# atmega328pTest.net
KiCad netlist of a schematic drawn in EAGLE
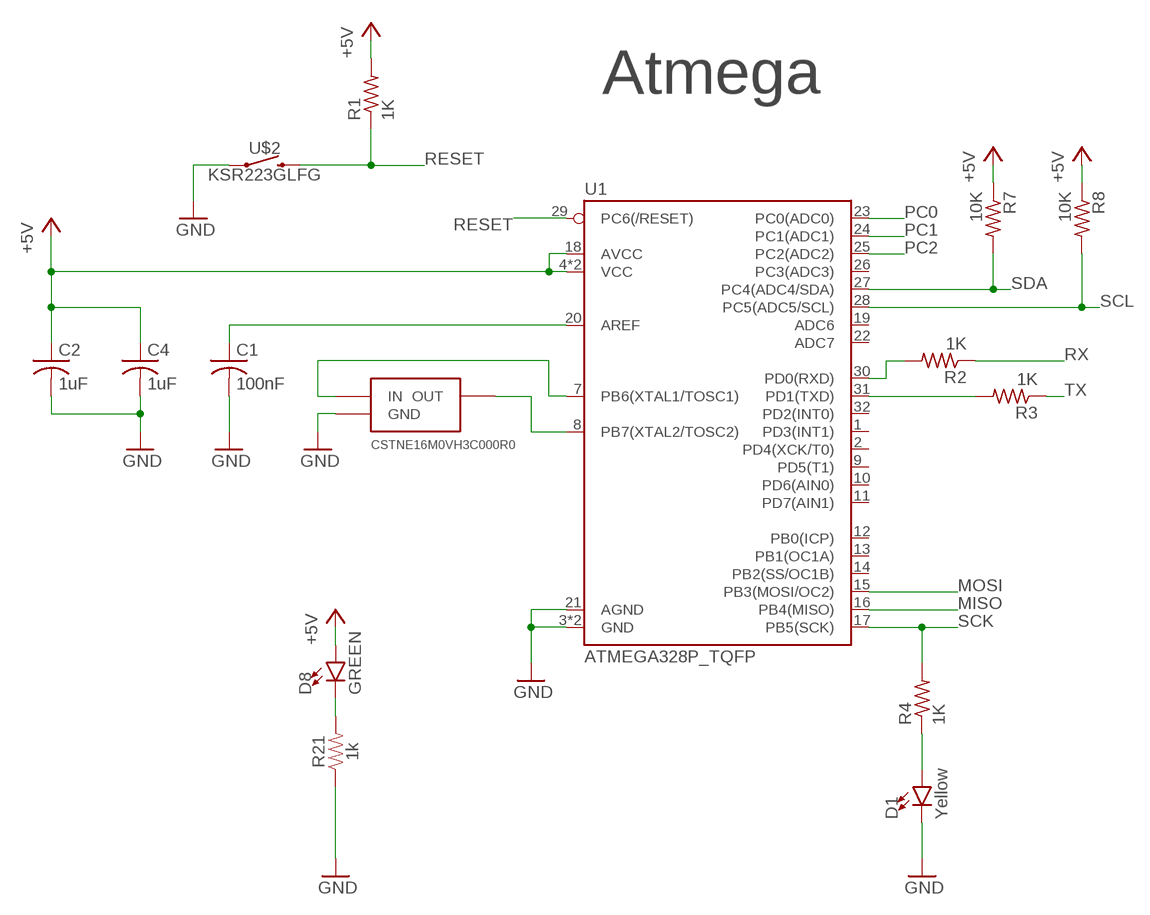
[diagram p0: schematic, sheet 1, part 1 of 2]
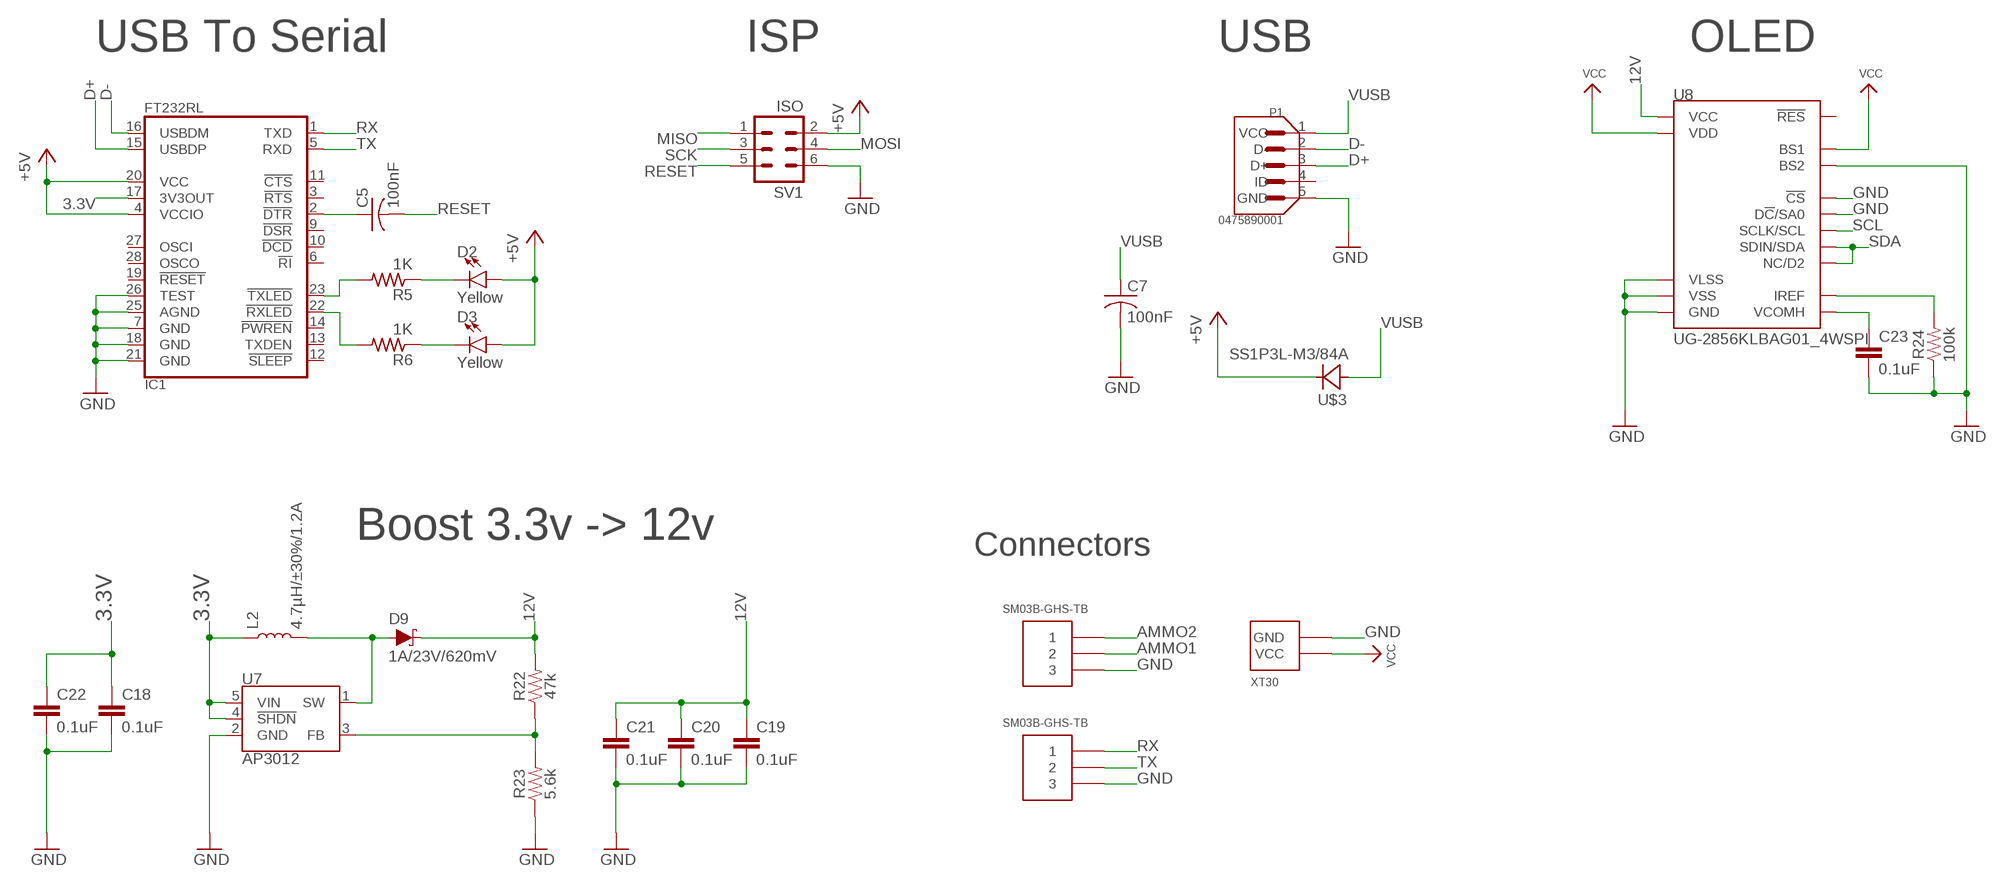
[diagram p1: schematic, sheet 1, part 2 of 2]

(export (version "E")
  (design (tool "Eeschema 10.0.6"))
  (components
    (comp (ref "C1")
      (value "100nF")
      (footprint "eagle-import:C0603")
      (libsource (lib "eagle-import") (part "C-USC0603"))
    )
    (comp (ref "C2")
      (value "1uF")
      (footprint "eagle-import:C0603")
      (libsource (lib "eagle-import") (part "C-USC0603"))
    )
    (comp (ref "C4")
      (value "1uF")
      (footprint "eagle-import:C0603")
      (libsource (lib "eagle-import") (part "C-USC0603"))
    )
    (comp (ref "C5")
      (value "100nF")
      (footprint "eagle-import:C0603")
      (libsource (lib "eagle-import") (part "C-USC0603"))
    )
    (comp (ref "C7")
      (value "100nF")
      (footprint "eagle-import:C0603")
      (libsource (lib "eagle-import") (part "C-USC0603"))
    )
    (comp (ref "C18")
      (value "0.1uF")
      (footprint "eagle-import:0603")
      (libsource (lib "eagle-import") (part "0.1UF-0603-25V-(+80/-20%)"))
    )
    (comp (ref "C19")
      (value "0.1uF")
      (footprint "eagle-import:0603")
      (libsource (lib "eagle-import") (part "0.1UF-0603-25V-(+80/-20%)"))
    )
    (comp (ref "C20")
      (value "0.1uF")
      (footprint "eagle-import:0603")
      (libsource (lib "eagle-import") (part "0.1UF-0603-25V-(+80/-20%)"))
    )
    (comp (ref "C21")
      (value "0.1uF")
      (footprint "eagle-import:0603")
      (libsource (lib "eagle-import") (part "0.1UF-0603-25V-(+80/-20%)"))
    )
    (comp (ref "C22")
      (value "0.1uF")
      (footprint "eagle-import:0603")
      (libsource (lib "eagle-import") (part "0.1UF-0603-25V-(+80/-20%)"))
    )
    (comp (ref "C23")
      (value "0.1uF")
      (footprint "eagle-import:0603")
      (libsource (lib "eagle-import") (part "0.1UF-0603-25V-(+80/-20%)"))
    )
    (comp (ref "D1")
      (value "Yellow")
      (footprint "eagle-import:LED-0603")
      (libsource (lib "eagle-import") (part "LED0603"))
    )
    (comp (ref "D2")
      (value "Yellow")
      (footprint "eagle-import:LED-0603")
      (libsource (lib "eagle-import") (part "LED0603"))
    )
    (comp (ref "D3")
      (value "Yellow")
      (footprint "eagle-import:LED-0603")
      (libsource (lib "eagle-import") (part "LED0603"))
    )
    (comp (ref "D8")
      (value "GREEN")
      (footprint "eagle-import:LED-0603")
      (libsource (lib "eagle-import") (part "SparkFun-LED_529_LED0603"))
    )
    (comp (ref "D9")
      (value "1A/23V/620mV")
      (footprint "eagle-import:SOD-323")
      (libsource (lib "eagle-import") (part "DIODE-SCHOTTKY-BAT20J"))
    )
    (comp (ref "IC1")
      (value "FT232RL")
      (footprint "eagle-import:SSOP28-LD")
      (fields (field (name "DIGI-KEY_PART_NUMBER") "768-1007-1-ND") (field (name "MF") "FTDI, Future"))
      (libsource (lib "eagle-import") (part "FT232RL"))
    )
    (comp (ref "L2")
      (value "4.7µH/±30%/1.2A")
      (footprint "eagle-import:INDUCTOR_4.7UH")
      (libsource (lib "eagle-import") (part "INDUCTOR-CDRH-4.7UH"))
    )
    (comp (ref "P1")
      (value "0475890001")
      (footprint "eagle-import:MOLEX_0475890001")
      (fields (field (name "DIGI-KEY_PART_NUMBER") "WM17143CT-ND") (field (name "MF") "Molex"))
      (libsource (lib "eagle-import") (part "0475890001"))
    )
    (comp (ref "R1")
      (value "1K")
      (footprint "eagle-import:R0603")
      (libsource (lib "eagle-import") (part "R-US_R0603"))
    )
    (comp (ref "R2")
      (value "1K")
      (footprint "eagle-import:R0603")
      (libsource (lib "eagle-import") (part "R-US_R0603"))
    )
    (comp (ref "R3")
      (value "1K")
      (footprint "eagle-import:R0603")
      (libsource (lib "eagle-import") (part "R-US_R0603"))
    )
    (comp (ref "R4")
      (value "1K")
      (footprint "eagle-import:R0603")
      (libsource (lib "eagle-import") (part "R-US_R0603"))
    )
    (comp (ref "R5")
      (value "1K")
      (footprint "eagle-import:R0603")
      (libsource (lib "eagle-import") (part "R-US_R0603"))
    )
    (comp (ref "R6")
      (value "1K")
      (footprint "eagle-import:R0603")
      (libsource (lib "eagle-import") (part "R-US_R0603"))
    )
    (comp (ref "R7")
      (value "10K")
      (footprint "eagle-import:R0603")
      (libsource (lib "eagle-import") (part "R-US_R0603"))
    )
    (comp (ref "R8")
      (value "10K")
      (footprint "eagle-import:R0603")
      (libsource (lib "eagle-import") (part "R-US_R0603"))
    )
    (comp (ref "R21")
      (value "1k")
      (footprint "eagle-import:0603")
      (libsource (lib "eagle-import") (part "1KOHM-0603-1/10W-1%"))
    )
    (comp (ref "R22")
      (value "47k")
      (footprint "eagle-import:0603")
      (libsource (lib "eagle-import") (part "47KOHM-0603-1/10W-1%"))
    )
    (comp (ref "R23")
      (value "5.6k")
      (footprint "eagle-import:0603")
      (libsource (lib "eagle-import") (part "5.6KOHM-0603-1/10W-1%"))
    )
    (comp (ref "R24")
      (value "100k")
      (footprint "eagle-import:0603")
      (libsource (lib "eagle-import") (part "100KOHM-0603-1/10W-1%"))
    )
    (comp (ref "SV1")
      (value "ISO")
      (footprint "eagle-import:MA03-2")
      (libsource (lib "eagle-import") (part "MA03-2"))
    )
    (comp (ref "U$1")
      (value "CSTNE16M0VH3C000R0")
      (footprint "eagle-import:CSTNE16M0VH3C000R0")
      (libsource (lib "eagle-import") (part "CSTNE16M0VH3C000R0"))
    )
    (comp (ref "U$2")
      (value "KSR223GLFG")
      (footprint "eagle-import:KSR223GLFG")
      (libsource (lib "eagle-import") (part "KSR223GLFG"))
    )
    (comp (ref "U$3")
      (value "SS1P3L-M3/84A")
      (footprint "eagle-import:SS1P3L-M3_84A")
      (libsource (lib "eagle-import") (part "SS1P3L-M3/84A"))
    )
    (comp (ref "U$13")
      (value "SM03B-GHS-TB")
      (footprint "eagle-import:SM03B-GHS-TB")
      (libsource (lib "eagle-import") (part "SM03B-GHS-TB"))
    )
    (comp (ref "U$14")
      (value "SM03B-GHS-TB")
      (footprint "eagle-import:SM03B-GHS-TB")
      (libsource (lib "eagle-import") (part "SM03B-GHS-TB"))
    )
    (comp (ref "U$15")
      (value "XT30PW-M")
      (footprint "eagle-import:XT30")
      (libsource (lib "eagle-import") (part "XT30PW-M"))
    )
    (comp (ref "U1")
      (value "ATMEGA328P_TQFP")
      (footprint "eagle-import:TQFP32-08")
      (libsource (lib "eagle-import") (part "ATMEGA328P_TQFP"))
    )
    (comp (ref "U7")
      (value "AP3012")
      (footprint "eagle-import:SOT23-5")
      (libsource (lib "eagle-import") (part "AP3012"))
    )
    (comp (ref "U8")
      (value "UG-2856KLBAG01_4WSPI")
      (footprint "eagle-import:FPC05024-42201")
      (libsource (lib "eagle-import") (part "UG-2856KLBAG01_4WSPI"))
    )
  )
  (nets
    (net (code "1") (name "+5V") (class "Default")
      (node (ref "C2") (pin "1") (pinfunction "1_1") (pintype "passive"))
      (node (ref "C4") (pin "1") (pinfunction "1_1") (pintype "passive"))
      (node (ref "D2") (pin "A") (pinfunction "A_A") (pintype "passive"))
      (node (ref "D3") (pin "A") (pinfunction "A_A") (pintype "passive"))
      (node (ref "D8") (pin "A") (pinfunction "A_A") (pintype "passive"))
      (node (ref "IC1") (pin "20") (pinfunction "VCC_20") (pintype "power_in"))
      (node (ref "IC1") (pin "4") (pinfunction "VCCIO_4") (pintype "power_in"))
      (node (ref "R1") (pin "2") (pinfunction "2_2") (pintype "passive"))
      (node (ref "R7") (pin "1") (pinfunction "1_1") (pintype "passive"))
      (node (ref "R8") (pin "1") (pinfunction "1_1") (pintype "passive"))
      (node (ref "SV1") (pin "2") (pinfunction "2_2") (pintype "passive"))
      (node (ref "U$3") (pin "P$1") (pinfunction "C_P$1") (pintype "passive"))
      (node (ref "U1") (pin "18") (pinfunction "AVCC_18") (pintype "bidirectional"))
      (node (ref "U1") (pin "4") (pinfunction "VCC_4") (pintype "bidirectional"))
      (node (ref "U1") (pin "6") (pinfunction "VCC_6") (pintype "bidirectional"))
    )
    (net (code "2") (name "/3.3V") (class "Default")
      (node (ref "C18") (pin "1") (pinfunction "1_1") (pintype "passive"))
      (node (ref "C22") (pin "1") (pinfunction "1_1") (pintype "passive"))
      (node (ref "IC1") (pin "17") (pinfunction "3V3OUT_17") (pintype "power_in"))
      (node (ref "L2") (pin "P$1") (pinfunction "1_P$1") (pintype "passive"))
      (node (ref "U7") (pin "4") (pinfunction "~{SHDN}_4") (pintype "bidirectional"))
      (node (ref "U7") (pin "5") (pinfunction "VIN_5") (pintype "bidirectional"))
    )
    (net (code "3") (name "/12V") (class "Default")
      (node (ref "C19") (pin "1") (pinfunction "1_1") (pintype "passive"))
      (node (ref "C20") (pin "1") (pinfunction "1_1") (pintype "passive"))
      (node (ref "C21") (pin "1") (pinfunction "1_1") (pintype "passive"))
      (node (ref "D9") (pin "C") (pinfunction "C_C") (pintype "passive"))
      (node (ref "R22") (pin "2") (pinfunction "2_2") (pintype "passive"))
      (node (ref "U8") (pin "P$23") (pinfunction "VCC_P$23") (pintype "bidirectional"))
    )
    (net (code "4") (name "/AMMO1") (class "Default")
      (node (ref "U$14") (pin "P$4") (pinfunction "2_P$4") (pintype "bidirectional"))
    )
    (net (code "5") (name "/AMMO2") (class "Default")
      (node (ref "U$14") (pin "P$3") (pinfunction "1_P$3") (pintype "bidirectional"))
    )
    (net (code "6") (name "/D+") (class "Default")
      (node (ref "IC1") (pin "15") (pinfunction "USBDP_15") (pintype "bidirectional"))
      (node (ref "P1") (pin "3") (pinfunction "D+_3") (pintype "bidirectional"))
    )
    (net (code "7") (name "/D-") (class "Default")
      (node (ref "IC1") (pin "16") (pinfunction "USBDM_16") (pintype "bidirectional"))
      (node (ref "P1") (pin "2") (pinfunction "D-_2") (pintype "bidirectional"))
    )
    (net (code "8") (name "/MISO") (class "Default")
      (node (ref "SV1") (pin "1") (pinfunction "1_1") (pintype "passive"))
      (node (ref "U1") (pin "16") (pinfunction "PB4(MISO)_16") (pintype "bidirectional"))
    )
    (net (code "9") (name "/MOSI") (class "Default")
      (node (ref "SV1") (pin "4") (pinfunction "4_4") (pintype "passive"))
      (node (ref "U1") (pin "15") (pinfunction "PB3(MOSI/OC2)_15") (pintype "bidirectional"))
    )
    (net (code "10") (name "/PC0") (class "Default")
      (node (ref "U1") (pin "23") (pinfunction "PC0(ADC0)_23") (pintype "bidirectional"))
    )
    (net (code "11") (name "/PC1") (class "Default")
      (node (ref "U1") (pin "24") (pinfunction "PC1(ADC1)_24") (pintype "bidirectional"))
    )
    (net (code "12") (name "/PC2") (class "Default")
      (node (ref "U1") (pin "25") (pinfunction "PC2(ADC2)_25") (pintype "bidirectional"))
    )
    (net (code "13") (name "/RESET") (class "Default")
      (node (ref "C5") (pin "2") (pinfunction "2_2") (pintype "passive"))
      (node (ref "R1") (pin "1") (pinfunction "1_1") (pintype "passive"))
      (node (ref "SV1") (pin "5") (pinfunction "5_5") (pintype "passive"))
      (node (ref "U$2") (pin "P$2") (pinfunction "2_P$2") (pintype "passive"))
      (node (ref "U1") (pin "29") (pinfunction "PC6(/RESET)_29") (pintype "bidirectional"))
    )
    (net (code "14") (name "/RX") (class "Default")
      (node (ref "IC1") (pin "1") (pinfunction "TXD_1") (pintype "output"))
      (node (ref "R2") (pin "1") (pinfunction "1_1") (pintype "passive"))
      (node (ref "U$13") (pin "P$3") (pinfunction "1_P$3") (pintype "bidirectional"))
    )
    (net (code "15") (name "/SCK") (class "Default")
      (node (ref "R4") (pin "2") (pinfunction "2_2") (pintype "passive"))
      (node (ref "SV1") (pin "3") (pinfunction "3_3") (pintype "passive"))
      (node (ref "U1") (pin "17") (pinfunction "PB5(SCK)_17") (pintype "bidirectional"))
    )
    (net (code "16") (name "/SCL") (class "Default")
      (node (ref "R8") (pin "2") (pinfunction "2_2") (pintype "passive"))
      (node (ref "U1") (pin "28") (pinfunction "PC5(ADC5/SCL)_28") (pintype "bidirectional"))
      (node (ref "U8") (pin "P$13") (pinfunction "SCLK/SCL_P$13") (pintype "bidirectional"))
    )
    (net (code "17") (name "/SDA") (class "Default")
      (node (ref "R7") (pin "2") (pinfunction "2_2") (pintype "passive"))
      (node (ref "U1") (pin "27") (pinfunction "PC4(ADC4/SDA)_27") (pintype "bidirectional"))
      (node (ref "U8") (pin "P$14") (pinfunction "SDIN/SDA_P$14") (pintype "bidirectional"))
      (node (ref "U8") (pin "P$15") (pinfunction "NC/D2_P$15") (pintype "bidirectional"))
    )
    (net (code "18") (name "/TX") (class "Default")
      (node (ref "IC1") (pin "5") (pinfunction "RXD_5") (pintype "input"))
      (node (ref "R3") (pin "1") (pinfunction "1_1") (pintype "passive"))
      (node (ref "U$13") (pin "P$4") (pinfunction "2_P$4") (pintype "bidirectional"))
    )
    (net (code "19") (name "/VUSB") (class "Default")
      (node (ref "C7") (pin "1") (pinfunction "1_1") (pintype "passive"))
      (node (ref "P1") (pin "1") (pinfunction "VCC_1") (pintype "power_in"))
      (node (ref "U$3") (pin "P$2") (pinfunction "A_P$2") (pintype "passive"))
    )
    (net (code "20") (name "GND") (class "Default")
      (node (ref "C1") (pin "2") (pinfunction "2_2") (pintype "passive"))
      (node (ref "C18") (pin "2") (pinfunction "2_2") (pintype "passive"))
      (node (ref "C19") (pin "2") (pinfunction "2_2") (pintype "passive"))
      (node (ref "C2") (pin "2") (pinfunction "2_2") (pintype "passive"))
      (node (ref "C20") (pin "2") (pinfunction "2_2") (pintype "passive"))
      (node (ref "C21") (pin "2") (pinfunction "2_2") (pintype "passive"))
      (node (ref "C22") (pin "2") (pinfunction "2_2") (pintype "passive"))
      (node (ref "C23") (pin "2") (pinfunction "2_2") (pintype "passive"))
      (node (ref "C4") (pin "2") (pinfunction "2_2") (pintype "passive"))
      (node (ref "C7") (pin "2") (pinfunction "2_2") (pintype "passive"))
      (node (ref "D1") (pin "C") (pinfunction "C_C") (pintype "passive"))
      (node (ref "IC1") (pin "18") (pinfunction "GND_18") (pintype "power_in"))
      (node (ref "IC1") (pin "21") (pinfunction "GND_21") (pintype "power_in"))
      (node (ref "IC1") (pin "25") (pinfunction "AGND_25") (pintype "power_in"))
      (node (ref "IC1") (pin "26") (pinfunction "TEST_26") (pintype "input"))
      (node (ref "IC1") (pin "7") (pinfunction "GND_7") (pintype "power_in"))
      (node (ref "P1") (pin "5") (pinfunction "GND_5") (pintype "power_in"))
      (node (ref "R21") (pin "1") (pinfunction "1_1") (pintype "passive"))
      (node (ref "R23") (pin "1") (pinfunction "1_1") (pintype "passive"))
      (node (ref "R24") (pin "1") (pinfunction "1_1") (pintype "passive"))
      (node (ref "SV1") (pin "6") (pinfunction "6_6") (pintype "passive"))
      (node (ref "U$1") (pin "2") (pinfunction "GND_2") (pintype "bidirectional"))
      (node (ref "U$13") (pin "P$5") (pinfunction "3_P$5") (pintype "bidirectional"))
      (node (ref "U$14") (pin "P$5") (pinfunction "3_P$5") (pintype "bidirectional"))
      (node (ref "U$15") (pin "P$2") (pinfunction "GND_P$2") (pintype "bidirectional"))
      (node (ref "U$2") (pin "P$1") (pinfunction "1_P$1") (pintype "passive"))
      (node (ref "U1") (pin "21") (pinfunction "AGND_21") (pintype "bidirectional"))
      (node (ref "U1") (pin "3") (pinfunction "GND_3") (pintype "bidirectional"))
      (node (ref "U1") (pin "5") (pinfunction "GND_5") (pintype "bidirectional"))
      (node (ref "U7") (pin "2") (pinfunction "GND_2") (pintype "bidirectional"))
      (node (ref "U8") (pin "P$1") (pinfunction "GND_P$1") (pintype "bidirectional"))
      (node (ref "U8") (pin "P$10") (pinfunction "D~{C}/SA0_P$10") (pintype "bidirectional"))
      (node (ref "U8") (pin "P$11") (pinfunction "GND_P$11") (pintype "bidirectional"))
      (node (ref "U8") (pin "P$12") (pinfunction "GND_P$12") (pintype "bidirectional"))
      (node (ref "U8") (pin "P$16") (pinfunction "GND_P$16") (pintype "bidirectional"))
      (node (ref "U8") (pin "P$17") (pinfunction "GND_P$17") (pintype "bidirectional"))
      (node (ref "U8") (pin "P$18") (pinfunction "GND_P$18") (pintype "bidirectional"))
      (node (ref "U8") (pin "P$19") (pinfunction "GND_P$19") (pintype "bidirectional"))
      (node (ref "U8") (pin "P$2") (pinfunction "VLSS_P$2") (pintype "bidirectional"))
      (node (ref "U8") (pin "P$20") (pinfunction "GND_P$20") (pintype "bidirectional"))
      (node (ref "U8") (pin "P$24") (pinfunction "GND_P$24") (pintype "bidirectional"))
      (node (ref "U8") (pin "P$3") (pinfunction "VSS_P$3") (pintype "bidirectional"))
      (node (ref "U8") (pin "P$7") (pinfunction "BS2_P$7") (pintype "bidirectional"))
      (node (ref "U8") (pin "P$8") (pinfunction "~{CS}_P$8") (pintype "bidirectional"))
    )
    (net (code "21") (name "Net-(D1-PadA)") (class "Default")
      (node (ref "D1") (pin "A") (pinfunction "A_A") (pintype "passive"))
      (node (ref "R4") (pin "1") (pinfunction "1_1") (pintype "passive"))
    )
    (net (code "22") (name "Net-(D2-PadC)") (class "Default")
      (node (ref "D2") (pin "C") (pinfunction "C_C") (pintype "passive"))
      (node (ref "R5") (pin "1") (pinfunction "1_1") (pintype "passive"))
    )
    (net (code "23") (name "Net-(D3-PadC)") (class "Default")
      (node (ref "D3") (pin "C") (pinfunction "C_C") (pintype "passive"))
      (node (ref "R6") (pin "1") (pinfunction "1_1") (pintype "passive"))
    )
    (net (code "24") (name "Net-(D8-PadC)") (class "Default")
      (node (ref "D8") (pin "C") (pinfunction "C_C") (pintype "passive"))
      (node (ref "R21") (pin "2") (pinfunction "2_2") (pintype "passive"))
    )
    (net (code "25") (name "Net-(IC1-~{DTR})") (class "Default")
      (node (ref "C5") (pin "1") (pinfunction "1_1") (pintype "passive"))
      (node (ref "IC1") (pin "2") (pinfunction "~{DTR}_2") (pintype "output"))
    )
    (net (code "26") (name "Net-(IC1-~{RXLED})") (class "Default")
      (node (ref "IC1") (pin "22") (pinfunction "~{RXLED}_22") (pintype "input"))
      (node (ref "R6") (pin "2") (pinfunction "2_2") (pintype "passive"))
    )
    (net (code "27") (name "Net-(IC1-~{TXLED})") (class "Default")
      (node (ref "IC1") (pin "23") (pinfunction "~{TXLED}_23") (pintype "input"))
      (node (ref "R5") (pin "2") (pinfunction "2_2") (pintype "passive"))
    )
    (net (code "28") (name "Net-(L2-2)") (class "Default")
      (node (ref "D9") (pin "A") (pinfunction "A_A") (pintype "passive"))
      (node (ref "L2") (pin "P$2") (pinfunction "2_P$2") (pintype "passive"))
      (node (ref "U7") (pin "1") (pinfunction "SW_1") (pintype "bidirectional"))
    )
    (net (code "29") (name "Net-(U$1-IN)") (class "Default")
      (node (ref "U$1") (pin "1") (pinfunction "IN_1") (pintype "bidirectional"))
      (node (ref "U1") (pin "7") (pinfunction "PB6(XTAL1/TOSC1)_7") (pintype "bidirectional"))
    )
    (net (code "30") (name "Net-(U$1-OUT)") (class "Default")
      (node (ref "U$1") (pin "3") (pinfunction "OUT_3") (pintype "bidirectional"))
      (node (ref "U1") (pin "8") (pinfunction "PB7(XTAL2/TOSC2)_8") (pintype "bidirectional"))
    )
    (net (code "31") (name "Net-(U1-AREF)") (class "Default")
      (node (ref "C1") (pin "1") (pinfunction "1_1") (pintype "passive"))
      (node (ref "U1") (pin "20") (pinfunction "AREF_20") (pintype "bidirectional"))
    )
    (net (code "32") (name "Net-(U1-PD0(RXD))") (class "Default")
      (node (ref "R2") (pin "2") (pinfunction "2_2") (pintype "passive"))
      (node (ref "U1") (pin "30") (pinfunction "PD0(RXD)_30") (pintype "bidirectional"))
    )
    (net (code "33") (name "Net-(U1-PD1(TXD))") (class "Default")
      (node (ref "R3") (pin "2") (pinfunction "2_2") (pintype "passive"))
      (node (ref "U1") (pin "31") (pinfunction "PD1(TXD)_31") (pintype "bidirectional"))
    )
    (net (code "34") (name "Net-(U7-FB)") (class "Default")
      (node (ref "R22") (pin "1") (pinfunction "1_1") (pintype "passive"))
      (node (ref "R23") (pin "2") (pinfunction "2_2") (pintype "passive"))
      (node (ref "U7") (pin "3") (pinfunction "FB_3") (pintype "bidirectional"))
    )
    (net (code "35") (name "Net-(U8-IREF)") (class "Default")
      (node (ref "R24") (pin "2") (pinfunction "2_2") (pintype "passive"))
      (node (ref "U8") (pin "P$21") (pinfunction "IREF_P$21") (pintype "bidirectional"))
    )
    (net (code "36") (name "Net-(U8-VCOMH)") (class "Default")
      (node (ref "C23") (pin "1") (pinfunction "1_1") (pintype "passive"))
      (node (ref "U8") (pin "P$22") (pinfunction "VCOMH_P$22") (pintype "bidirectional"))
    )
    (net (code "37") (name "VCC") (class "Default")
      (node (ref "U$15") (pin "P$1") (pinfunction "VCC_P$1") (pintype "bidirectional"))
      (node (ref "U8") (pin "P$5") (pinfunction "VDD_P$5") (pintype "bidirectional"))
      (node (ref "U8") (pin "P$6") (pinfunction "BS1_P$6") (pintype "bidirectional"))
    )
    (net (code "38") (name "unconnected-(IC1-OSCI-Pad27)") (class "Default")
      (node (ref "IC1") (pin "27") (pinfunction "OSCI_27") (pintype "no_connect"))
    )
    (net (code "39") (name "unconnected-(IC1-OSCO-Pad28)") (class "Default")
      (node (ref "IC1") (pin "28") (pinfunction "OSCO_28") (pintype "output"))
    )
    (net (code "40") (name "unconnected-(IC1-TXDEN-Pad13)") (class "Default")
      (node (ref "IC1") (pin "13") (pinfunction "TXDEN_13") (pintype "no_connect"))
    )
    (net (code "41") (name "unconnected-(IC1-~{CTS}-Pad11)") (class "Default")
      (node (ref "IC1") (pin "11") (pinfunction "~{CTS}_11") (pintype "input"))
    )
    (net (code "42") (name "unconnected-(IC1-~{DCD}-Pad10)") (class "Default")
      (node (ref "IC1") (pin "10") (pinfunction "~{DCD}_10") (pintype "no_connect"))
    )
    (net (code "43") (name "unconnected-(IC1-~{DSR}-Pad9)") (class "Default")
      (node (ref "IC1") (pin "9") (pinfunction "~{DSR}_9") (pintype "no_connect"))
    )
    (net (code "44") (name "unconnected-(IC1-~{PWREN}-Pad14)") (class "Default")
      (node (ref "IC1") (pin "14") (pinfunction "~{PWREN}_14") (pintype "no_connect"))
    )
    (net (code "45") (name "unconnected-(IC1-~{RESET}-Pad19)") (class "Default")
      (node (ref "IC1") (pin "19") (pinfunction "~{RESET}_19") (pintype "no_connect"))
    )
    (net (code "46") (name "unconnected-(IC1-~{RI}-Pad6)") (class "Default")
      (node (ref "IC1") (pin "6") (pinfunction "~{RI}_6") (pintype "no_connect"))
    )
    (net (code "47") (name "unconnected-(IC1-~{RTS}-Pad3)") (class "Default")
      (node (ref "IC1") (pin "3") (pinfunction "~{RTS}_3") (pintype "output"))
    )
    (net (code "48") (name "unconnected-(IC1-~{SLEEP}-Pad12)") (class "Default")
      (node (ref "IC1") (pin "12") (pinfunction "~{SLEEP}_12") (pintype "no_connect"))
    )
    (net (code "49") (name "unconnected-(P1-ID-Pad4)") (class "Default")
      (node (ref "P1") (pin "4") (pinfunction "ID_4") (pintype "bidirectional"))
    )
    (net (code "50") (name "unconnected-(U1-ADC6-Pad19)") (class "Default")
      (node (ref "U1") (pin "19") (pinfunction "ADC6_19") (pintype "bidirectional"))
    )
    (net (code "51") (name "unconnected-(U1-ADC7-Pad22)") (class "Default")
      (node (ref "U1") (pin "22") (pinfunction "ADC7_22") (pintype "bidirectional"))
    )
    (net (code "52") (name "unconnected-(U1-PB0(ICP)-Pad12)") (class "Default")
      (node (ref "U1") (pin "12") (pinfunction "PB0(ICP)_12") (pintype "bidirectional"))
    )
    (net (code "53") (name "unconnected-(U1-PB1(OC1A)-Pad13)") (class "Default")
      (node (ref "U1") (pin "13") (pinfunction "PB1(OC1A)_13") (pintype "bidirectional"))
    )
    (net (code "54") (name "unconnected-(U1-PB2(SS{slash}OC1B)-Pad14)") (class "Default")
      (node (ref "U1") (pin "14") (pinfunction "PB2(SS/OC1B)_14") (pintype "bidirectional"))
    )
    (net (code "55") (name "unconnected-(U1-PC3(ADC3)-Pad26)") (class "Default")
      (node (ref "U1") (pin "26") (pinfunction "PC3(ADC3)_26") (pintype "bidirectional"))
    )
    (net (code "56") (name "unconnected-(U1-PD2(INT0)-Pad32)") (class "Default")
      (node (ref "U1") (pin "32") (pinfunction "PD2(INT0)_32") (pintype "bidirectional"))
    )
    (net (code "57") (name "unconnected-(U1-PD3(INT1)-Pad1)") (class "Default")
      (node (ref "U1") (pin "1") (pinfunction "PD3(INT1)_1") (pintype "bidirectional"))
    )
    (net (code "58") (name "unconnected-(U1-PD4(XCK{slash}T0)-Pad2)") (class "Default")
      (node (ref "U1") (pin "2") (pinfunction "PD4(XCK/T0)_2") (pintype "bidirectional"))
    )
    (net (code "59") (name "unconnected-(U1-PD5(T1)-Pad9)") (class "Default")
      (node (ref "U1") (pin "9") (pinfunction "PD5(T1)_9") (pintype "bidirectional"))
    )
    (net (code "60") (name "unconnected-(U1-PD6(AIN0)-Pad10)") (class "Default")
      (node (ref "U1") (pin "10") (pinfunction "PD6(AIN0)_10") (pintype "bidirectional"))
    )
    (net (code "61") (name "unconnected-(U1-PD7(AIN1)-Pad11)") (class "Default")
      (node (ref "U1") (pin "11") (pinfunction "PD7(AIN1)_11") (pintype "bidirectional"))
    )
    (net (code "62") (name "unconnected-(U8-~{RES}-PadP$9)") (class "Default")
      (node (ref "U8") (pin "P$9") (pinfunction "~{RES}_P$9") (pintype "bidirectional"))
    )
  )
)
